# acms_project_starter_template.net
KiCad netlist of a schematic drawn in EAGLE
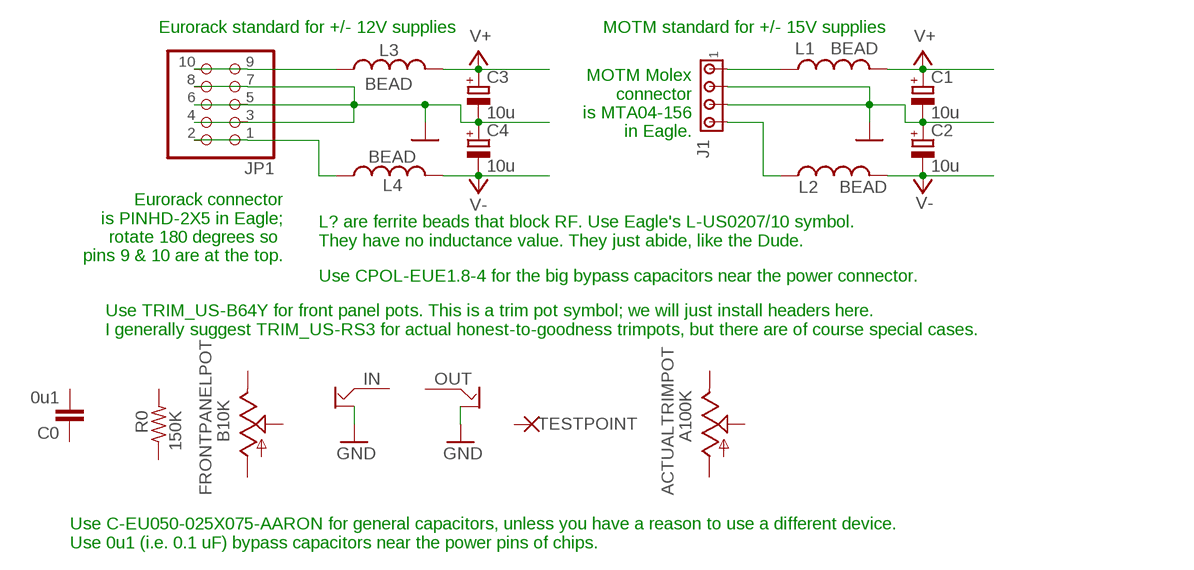
[diagram p0: schematic, sheet 1]

(export (version "E")
  (design (tool "Eeschema 10.0.6"))
  (components
    (comp (ref "ACTUALTRIMPOT")
      (value "A100K")
      (footprint "eagle-import:RS3")
      (libsource (lib "eagle-import") (part "pot_331_TRIM_US-RS3"))
    )
    (comp (ref "C0")
      (value "0u1")
      (footprint "eagle-import:C050-025X075-AARON")
      (libsource (lib "eagle-import") (part "C-EU050-025X075-AARON"))
    )
    (comp (ref "C1")
      (value "10u")
      (footprint "eagle-import:E1,8-4")
      (libsource (lib "eagle-import") (part "CPOL-EUE1.8-4"))
    )
    (comp (ref "C2")
      (value "10u")
      (footprint "eagle-import:E1,8-4")
      (libsource (lib "eagle-import") (part "CPOL-EUE1.8-4"))
    )
    (comp (ref "C3")
      (value "10u")
      (footprint "eagle-import:E1,8-4")
      (libsource (lib "eagle-import") (part "CPOL-EUE1.8-4"))
    )
    (comp (ref "C4")
      (value "10u")
      (footprint "eagle-import:E1,8-4")
      (libsource (lib "eagle-import") (part "CPOL-EUE1.8-4"))
    )
    (comp (ref "FRONTPANELPOT")
      (value "B10K")
      (footprint "eagle-import:B64Y")
      (libsource (lib "eagle-import") (part "TRIM_US-B64Y"))
    )
    (comp (ref "IN")
      (value "OFFBOARD2JACKALT_AARON")
      (footprint "eagle-import:OFFBOARD2JACKALT")
      (libsource (lib "eagle-import") (part "OFFBOARD2JACKALT_AARON"))
    )
    (comp (ref "J1")
      (value "MTA04-156")
      (footprint "eagle-import:1X4MTA")
      (libsource (lib "eagle-import") (part "MTA04-156"))
    )
    (comp (ref "JP1")
      (value "PINHD-2X5")
      (footprint "eagle-import:2X05")
      (libsource (lib "eagle-import") (part "PINHD-2X5"))
    )
    (comp (ref "L1")
      (value "BEAD")
      (footprint "eagle-import:0207_10")
      (libsource (lib "eagle-import") (part "L-US0207/10"))
    )
    (comp (ref "L2")
      (value "BEAD")
      (footprint "eagle-import:0207_10")
      (libsource (lib "eagle-import") (part "L-US0207/10"))
    )
    (comp (ref "L3")
      (value "BEAD")
      (footprint "eagle-import:0207_10")
      (libsource (lib "eagle-import") (part "L-US0207/10"))
    )
    (comp (ref "L4")
      (value "BEAD")
      (footprint "eagle-import:0207_10")
      (libsource (lib "eagle-import") (part "L-US0207/10"))
    )
    (comp (ref "OUT")
      (value "OFFBOARD2JACKALT_AARON")
      (footprint "eagle-import:OFFBOARD2JACKALT")
      (libsource (lib "eagle-import") (part "OFFBOARD2JACKALT_AARON"))
    )
    (comp (ref "R0")
      (value "150K")
      (footprint "eagle-import:0207_10")
      (libsource (lib "eagle-import") (part "R-US_0207/10"))
    )
    (comp (ref "TESTPOINT")
      (value "IOPAD_AARON")
      (footprint "eagle-import:ELLIPTICALPADSINGLE")
      (libsource (lib "eagle-import") (part "IOPAD_AARON"))
    )
  )
  (nets
    (net (code "1") (name "GND") (class "Default")
      (node (ref "C1") (pin "-") (pinfunction "-_-") (pintype "passive"))
      (node (ref "C2") (pin "+") (pinfunction "+_+") (pintype "passive"))
      (node (ref "C3") (pin "-") (pinfunction "-_-") (pintype "passive"))
      (node (ref "C4") (pin "+") (pinfunction "+_+") (pintype "passive"))
      (node (ref "IN") (pin "GND") (pinfunction "GND_GND") (pintype "passive"))
      (node (ref "J1") (pin "2") (pinfunction "2_2") (pintype "passive"))
      (node (ref "J1") (pin "3") (pinfunction "3_3") (pintype "passive"))
      (node (ref "JP1") (pin "3") (pinfunction "3_3") (pintype "passive"))
      (node (ref "JP1") (pin "4") (pinfunction "4_4") (pintype "passive"))
      (node (ref "JP1") (pin "5") (pinfunction "5_5") (pintype "passive"))
      (node (ref "JP1") (pin "6") (pinfunction "6_6") (pintype "passive"))
      (node (ref "JP1") (pin "7") (pinfunction "7_7") (pintype "passive"))
      (node (ref "JP1") (pin "8") (pinfunction "8_8") (pintype "passive"))
      (node (ref "OUT") (pin "GND") (pinfunction "GND_GND") (pintype "passive"))
    )
    (net (code "2") (name "Net-(J1-Pad1)") (class "Default")
      (node (ref "J1") (pin "1") (pinfunction "1_1") (pintype "passive"))
      (node (ref "L1") (pin "1") (pinfunction "1_1") (pintype "passive"))
    )
    (net (code "3") (name "Net-(J1-Pad4)") (class "Default")
      (node (ref "J1") (pin "4") (pinfunction "4_4") (pintype "passive"))
      (node (ref "L2") (pin "1") (pinfunction "1_1") (pintype "passive"))
    )
    (net (code "4") (name "Net-(JP1-Pad1)") (class "Default")
      (node (ref "JP1") (pin "1") (pinfunction "1_1") (pintype "passive"))
      (node (ref "JP1") (pin "2") (pinfunction "2_2") (pintype "passive"))
      (node (ref "L4") (pin "1") (pinfunction "1_1") (pintype "passive"))
    )
    (net (code "5") (name "Net-(JP1-Pad10)") (class "Default")
      (node (ref "JP1") (pin "10") (pinfunction "10_10") (pintype "passive"))
      (node (ref "JP1") (pin "9") (pinfunction "9_9") (pintype "passive"))
      (node (ref "L3") (pin "1") (pinfunction "1_1") (pintype "passive"))
    )
    (net (code "6") (name "V+") (class "Default")
      (node (ref "C1") (pin "+") (pinfunction "+_+") (pintype "passive"))
      (node (ref "C3") (pin "+") (pinfunction "+_+") (pintype "passive"))
      (node (ref "L1") (pin "2") (pinfunction "2_2") (pintype "passive"))
      (node (ref "L3") (pin "2") (pinfunction "2_2") (pintype "passive"))
    )
    (net (code "7") (name "V-") (class "Default")
      (node (ref "C2") (pin "-") (pinfunction "-_-") (pintype "passive"))
      (node (ref "C4") (pin "-") (pinfunction "-_-") (pintype "passive"))
      (node (ref "L2") (pin "2") (pinfunction "2_2") (pintype "passive"))
      (node (ref "L4") (pin "2") (pinfunction "2_2") (pintype "passive"))
    )
    (net (code "8") (name "unconnected-(ACTUALTRIMPOT-PadA)") (class "Default")
      (node (ref "ACTUALTRIMPOT") (pin "A") (pinfunction "A_A") (pintype "passive"))
    )
    (net (code "9") (name "unconnected-(ACTUALTRIMPOT-PadE)") (class "Default")
      (node (ref "ACTUALTRIMPOT") (pin "E") (pinfunction "E_E") (pintype "passive"))
    )
    (net (code "10") (name "unconnected-(ACTUALTRIMPOT-PadS)") (class "Default")
      (node (ref "ACTUALTRIMPOT") (pin "S") (pinfunction "S_S") (pintype "passive"))
    )
    (net (code "11") (name "unconnected-(C0-Pad1)") (class "Default")
      (node (ref "C0") (pin "1") (pinfunction "1_1") (pintype "passive"))
    )
    (net (code "12") (name "unconnected-(C0-Pad2)") (class "Default")
      (node (ref "C0") (pin "2") (pinfunction "2_2") (pintype "passive"))
    )
    (net (code "13") (name "unconnected-(FRONTPANELPOT-PadA)") (class "Default")
      (node (ref "FRONTPANELPOT") (pin "A") (pinfunction "A_A") (pintype "passive"))
    )
    (net (code "14") (name "unconnected-(FRONTPANELPOT-PadE)") (class "Default")
      (node (ref "FRONTPANELPOT") (pin "E") (pinfunction "E_E") (pintype "passive"))
    )
    (net (code "15") (name "unconnected-(FRONTPANELPOT-PadS)") (class "Default")
      (node (ref "FRONTPANELPOT") (pin "S") (pinfunction "S_S") (pintype "passive"))
    )
    (net (code "16") (name "unconnected-(IN-PadSIGNAL)") (class "Default")
      (node (ref "IN") (pin "SIGNAL") (pinfunction "SIGNAL_SIGNAL") (pintype "passive"))
    )
    (net (code "17") (name "unconnected-(OUT-PadSIGNAL)") (class "Default")
      (node (ref "OUT") (pin "SIGNAL") (pinfunction "SIGNAL_SIGNAL") (pintype "passive"))
    )
    (net (code "18") (name "unconnected-(R0-Pad1)") (class "Default")
      (node (ref "R0") (pin "1") (pinfunction "1_1") (pintype "passive"))
    )
    (net (code "19") (name "unconnected-(R0-Pad2)") (class "Default")
      (node (ref "R0") (pin "2") (pinfunction "2_2") (pintype "passive"))
    )
    (net (code "20") (name "unconnected-(TESTPOINT-P-PadP$1)") (class "Default")
      (node (ref "TESTPOINT") (pin "P$1") (pinfunction "P_P$1") (pintype "passive"))
    )
  )
)
